# Motor.net
KiCad netlist of a schematic drawn in EasyEDA Pro
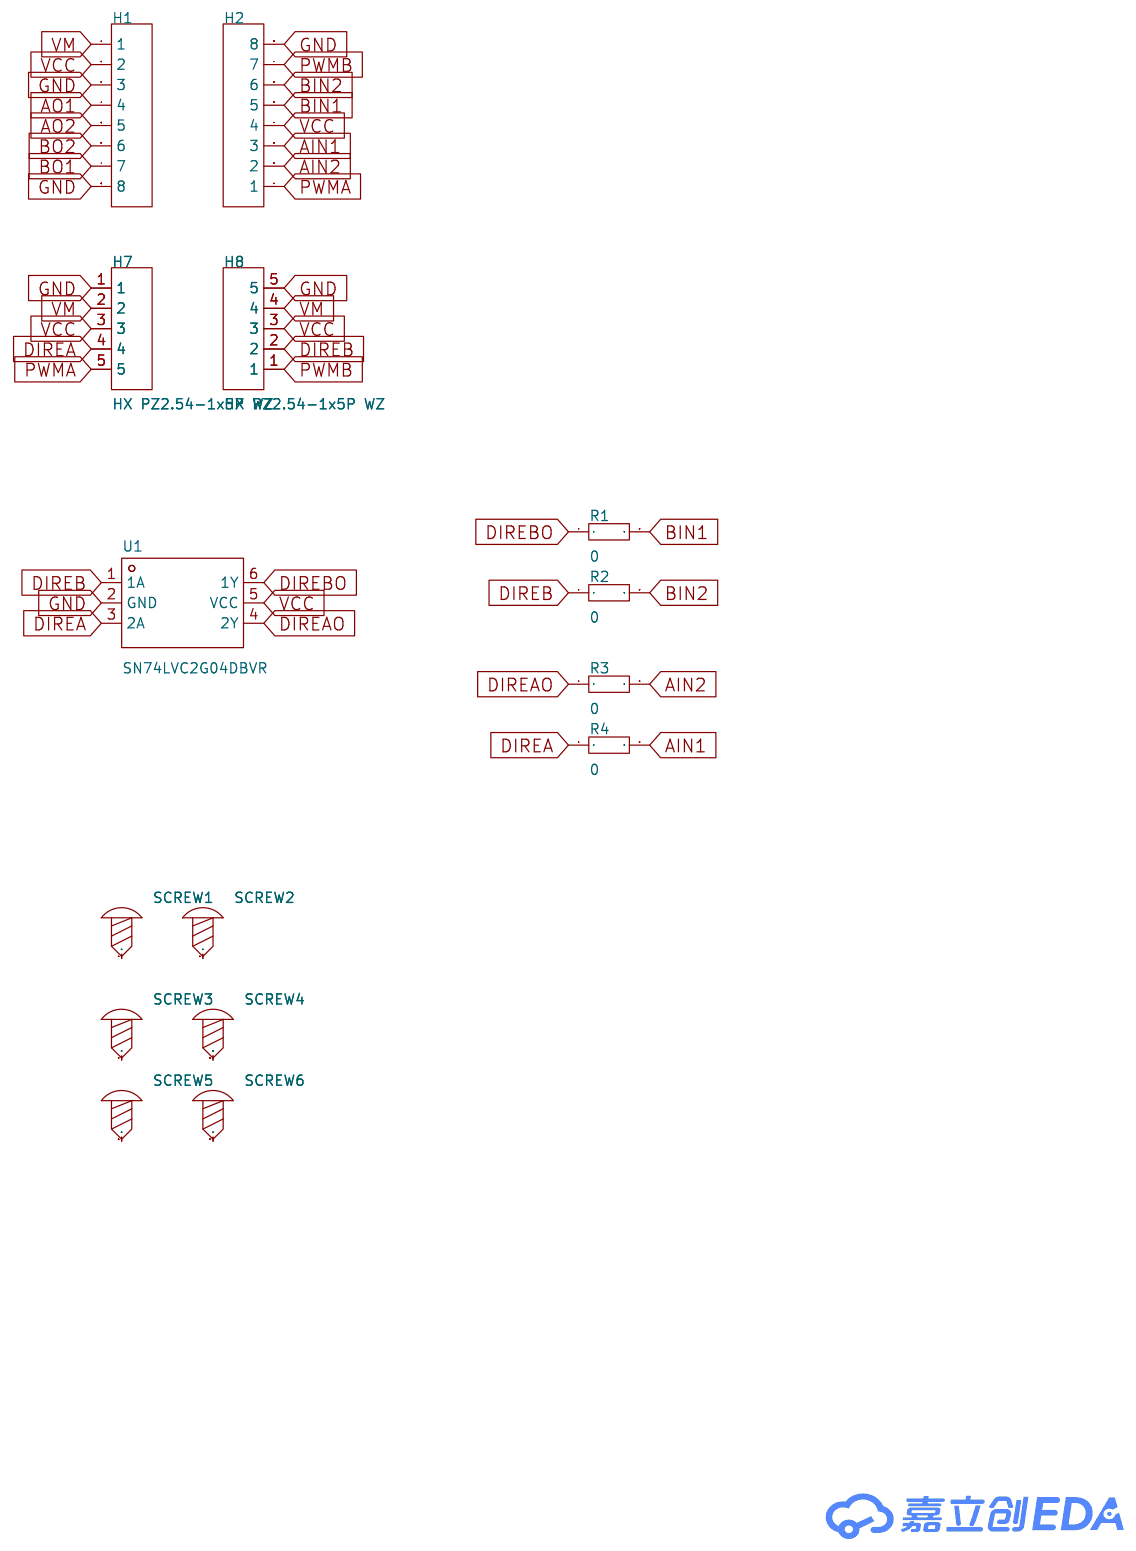
[diagram p0: schematic sheet]

(export (version "E")
  (design (tool "Eeschema 10.0.6"))
  (components
    (comp (ref "H1")
      (value "~")
      (footprint "easyedapro:HDR-TH_8P-P2.54-V-F-1")
      (libsource (lib "easyedapro") (part "Header-Female-2.54_1x8"))
    )
    (comp (ref "H2")
      (value "~")
      (footprint "easyedapro:HDR-TH_8P-P2.54-V-F-1")
      (libsource (lib "easyedapro") (part "Header-Female-2.54_1x8"))
    )
    (comp (ref "H7")
      (value "HX PZ2.54-1x5P WZ")
      (footprint "easyedapro:HDR-TH_5P-P2.54-H-M-W10.0-N")
      (fields (field (name "Manufacturer") "hanxia(韩下)"))
      (libsource (lib "easyedapro") (part "HX PZ2.54-1X5P WZ"))
    )
    (comp (ref "H8")
      (value "HX PZ2.54-1x5P WZ")
      (footprint "easyedapro:HDR-TH_5P-P2.54-H-M-W10.0-N")
      (fields (field (name "Manufacturer") "hanxia(韩下)"))
      (libsource (lib "easyedapro") (part "HX PZ2.54-1X5P WZ"))
    )
    (comp (ref "R1") (value "0") (footprint "easyedapro:R0805") (libsource (lib "easyedapro") (part "电阻")))
    (comp (ref "R2") (value "0") (footprint "easyedapro:R0805") (libsource (lib "easyedapro") (part "电阻")))
    (comp (ref "R3") (value "0") (footprint "easyedapro:R0805") (libsource (lib "easyedapro") (part "电阻")))
    (comp (ref "R4") (value "0") (footprint "easyedapro:R0805") (libsource (lib "easyedapro") (part "电阻")))
    (comp (ref "SCREW1")
      (value "~")
      (footprint "easyedapro:M2螺丝")
      (libsource (lib "easyedapro") (part "螺丝孔"))
    )
    (comp (ref "SCREW2")
      (value "~")
      (footprint "easyedapro:M2螺丝")
      (libsource (lib "easyedapro") (part "螺丝孔"))
    )
    (comp (ref "SCREW3")
      (value "~")
      (footprint "easyedapro:M2螺丝")
      (libsource (lib "easyedapro") (part "螺丝孔"))
    )
    (comp (ref "SCREW4")
      (value "~")
      (footprint "easyedapro:M2螺丝")
      (libsource (lib "easyedapro") (part "螺丝孔"))
    )
    (comp (ref "SCREW5")
      (value "~")
      (footprint "easyedapro:M2螺丝")
      (libsource (lib "easyedapro") (part "螺丝孔"))
    )
    (comp (ref "SCREW6")
      (value "~")
      (footprint "easyedapro:M2螺丝")
      (libsource (lib "easyedapro") (part "螺丝孔"))
    )
    (comp (ref "U1")
      (value "SN74LVC2G04DBVR")
      (footprint "easyedapro:SOT-23-6_L2.9-W1.6-P0.95-LS2.8-BR")
      (description "工作电压:1.65V~5.5V;工作电流:10uA;通道数:2;传播延迟(tpd):3.2ns@5V,50pF;")
      (fields (field (name "Manufacturer") "TI(德州仪器)"))
      (libsource (lib "easyedapro") (part "SN74LVC2G04DBVR"))
    )
  )
  (nets
    (net (code "1") (name "AIN1") (class "Default")
      (node (ref "H2") (pin "3") (pinfunction "3_3") (pintype "input"))
      (node (ref "R4") (pin "2") (pinfunction "2_2") (pintype "input"))
    )
    (net (code "2") (name "AIN2") (class "Default")
      (node (ref "H2") (pin "2") (pinfunction "2_2") (pintype "input"))
      (node (ref "R3") (pin "2") (pinfunction "2_2") (pintype "input"))
    )
    (net (code "3") (name "AO1") (class "Default")
      (node (ref "H1") (pin "4") (pinfunction "4_4") (pintype "input"))
    )
    (net (code "4") (name "AO2") (class "Default")
      (node (ref "H1") (pin "5") (pinfunction "5_5") (pintype "input"))
    )
    (net (code "5") (name "BIN1") (class "Default")
      (node (ref "H2") (pin "5") (pinfunction "5_5") (pintype "input"))
      (node (ref "R1") (pin "2") (pinfunction "2_2") (pintype "input"))
    )
    (net (code "6") (name "BIN2") (class "Default")
      (node (ref "H2") (pin "6") (pinfunction "6_6") (pintype "input"))
      (node (ref "R2") (pin "2") (pinfunction "2_2") (pintype "input"))
    )
    (net (code "7") (name "BO1") (class "Default")
      (node (ref "H1") (pin "7") (pinfunction "7_7") (pintype "input"))
    )
    (net (code "8") (name "BO2") (class "Default")
      (node (ref "H1") (pin "6") (pinfunction "6_6") (pintype "input"))
    )
    (net (code "9") (name "DIREA") (class "Default")
      (node (ref "H7") (pin "4") (pinfunction "4_4") (pintype "unspecified"))
      (node (ref "R4") (pin "1") (pinfunction "1_1") (pintype "input"))
      (node (ref "U1") (pin "3") (pinfunction "2A_3") (pintype "unspecified"))
    )
    (net (code "10") (name "DIREAO") (class "Default")
      (node (ref "R3") (pin "1") (pinfunction "1_1") (pintype "input"))
      (node (ref "U1") (pin "4") (pinfunction "2Y_4") (pintype "unspecified"))
    )
    (net (code "11") (name "DIREB") (class "Default")
      (node (ref "H8") (pin "2") (pinfunction "2_2") (pintype "unspecified"))
      (node (ref "R2") (pin "1") (pinfunction "1_1") (pintype "input"))
      (node (ref "U1") (pin "1") (pinfunction "1A_1") (pintype "unspecified"))
    )
    (net (code "12") (name "DIREBO") (class "Default")
      (node (ref "R1") (pin "1") (pinfunction "1_1") (pintype "input"))
      (node (ref "U1") (pin "6") (pinfunction "1Y_6") (pintype "unspecified"))
    )
    (net (code "13") (name "GND") (class "Default")
      (node (ref "H1") (pin "3") (pinfunction "3_3") (pintype "input"))
      (node (ref "H1") (pin "8") (pinfunction "8_8") (pintype "input"))
      (node (ref "H2") (pin "8") (pinfunction "8_8") (pintype "input"))
      (node (ref "H7") (pin "1") (pinfunction "1_1") (pintype "unspecified"))
      (node (ref "H8") (pin "5") (pinfunction "5_5") (pintype "unspecified"))
      (node (ref "U1") (pin "2") (pinfunction "GND_2") (pintype "unspecified"))
    )
    (net (code "14") (name "PWMA") (class "Default")
      (node (ref "H2") (pin "1") (pinfunction "1_1") (pintype "input"))
      (node (ref "H7") (pin "5") (pinfunction "5_5") (pintype "unspecified"))
    )
    (net (code "15") (name "PWMB") (class "Default")
      (node (ref "H2") (pin "7") (pinfunction "7_7") (pintype "input"))
      (node (ref "H8") (pin "1") (pinfunction "1_1") (pintype "unspecified"))
    )
    (net (code "16") (name "VCC") (class "Default")
      (node (ref "H1") (pin "2") (pinfunction "2_2") (pintype "input"))
      (node (ref "H2") (pin "4") (pinfunction "4_4") (pintype "input"))
      (node (ref "H7") (pin "3") (pinfunction "3_3") (pintype "unspecified"))
      (node (ref "H8") (pin "3") (pinfunction "3_3") (pintype "unspecified"))
      (node (ref "U1") (pin "5") (pinfunction "VCC_5") (pintype "unspecified"))
    )
    (net (code "17") (name "VM") (class "Default")
      (node (ref "H1") (pin "1") (pinfunction "1_1") (pintype "input"))
      (node (ref "H7") (pin "2") (pinfunction "2_2") (pintype "unspecified"))
      (node (ref "H8") (pin "4") (pinfunction "4_4") (pintype "unspecified"))
    )
    (net (code "18") (name "unconnected-(SCREW1-Pad1)") (class "Default")
      (node (ref "SCREW1") (pin "1") (pinfunction "1_1") (pintype "input"))
    )
    (net (code "19") (name "unconnected-(SCREW2-Pad1)") (class "Default")
      (node (ref "SCREW2") (pin "1") (pinfunction "1_1") (pintype "input"))
    )
    (net (code "20") (name "unconnected-(SCREW3-Pad1)") (class "Default")
      (node (ref "SCREW3") (pin "1") (pinfunction "1_1") (pintype "input"))
    )
    (net (code "21") (name "unconnected-(SCREW4-Pad1)") (class "Default")
      (node (ref "SCREW4") (pin "1") (pinfunction "1_1") (pintype "input"))
    )
    (net (code "22") (name "unconnected-(SCREW5-Pad1)") (class "Default")
      (node (ref "SCREW5") (pin "1") (pinfunction "1_1") (pintype "input"))
    )
    (net (code "23") (name "unconnected-(SCREW6-Pad1)") (class "Default")
      (node (ref "SCREW6") (pin "1") (pinfunction "1_1") (pintype "input"))
    )
  )
)
